# SHDN-CURRENT-S12-V00-Buzzer.net
KiCad netlist of a schematic drawn in Altium Designer
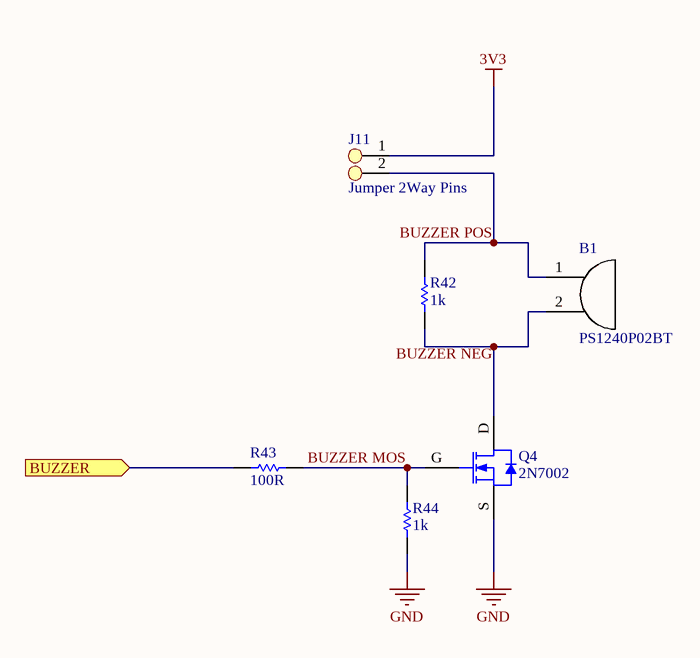
[diagram p0: SHDN-CURRENT-S12-V00-Buzzer.SchDoc]

(export (version "E")
  (design (tool "Eeschema 10.0.6"))
  (components
    (comp (ref "B1")
      (value "PS1240P02BT")
      (footprint "PS1240P02BT")
      (description "Buzzers Transducer, Externally Driven Piezo 3V 4kHz 60dB @ 3V, 10cm Through Hole PC Pins")
      (libsource (lib "QUTMS_BuzzerLibrary") (part "PS1240P02BT"))
    )
    (comp (ref "J11")
      (value "Jumper 2Way Pins")
      (footprint "Jumper_2Way_Pin")
      (description "Jumper 2Way Side Pins")
      (libsource (lib "QUTMS_JumperLibrary") (part "Jumper 2Way Side Pins"))
    )
    (comp (ref "Q4")
      (value "2N7002")
      (footprint "SOT23-3")
      (libsource (lib "QUTMS_MOSFETLibrary") (part "2N7002"))
    )
    (comp (ref "R42")
      (value "1k")
      (footprint "Res_ThinFilm_0603")
      (description "Resistor, SMD, 1k, 0.1W, 5%, 0603")
      (libsource (lib "StandardResistors") (part "1k 5% 0603"))
    )
    (comp (ref "R43")
      (value "100R")
      (footprint "Res_ThinFilm_0603")
      (description "Resistor, SMD, 100R, 0.1W, 5%, 0603")
      (libsource (lib "StandardResistors") (part "100R 5%, 0603"))
    )
    (comp (ref "R44")
      (value "1k")
      (footprint "Res_ThinFilm_0603")
      (description "Resistor, SMD, 1k, 0.1W, 5%, 0603")
      (libsource (lib "StandardResistors") (part "1k 5% 0603"))
    )
  )
  (nets
    (net (code "1") (name "/BUZZER") (class "Default")
      (node (ref "R43") (pin "1") (pinfunction "1_1") (pintype "passive"))
    )
    (net (code "2") (name "/BUZZER MOS") (class "Default")
      (node (ref "Q4") (pin "G") (pinfunction "G_G") (pintype "passive"))
      (node (ref "R43") (pin "2") (pinfunction "2_2") (pintype "passive"))
      (node (ref "R44") (pin "1") (pinfunction "1_1") (pintype "passive"))
    )
    (net (code "3") (name "/BUZZER NEG") (class "Default")
      (node (ref "B1") (pin "2") (pinfunction "2_2") (pintype "passive"))
      (node (ref "Q4") (pin "D") (pinfunction "D_D") (pintype "passive"))
      (node (ref "R42") (pin "1") (pinfunction "1_1") (pintype "passive"))
    )
    (net (code "4") (name "/BUZZER POS") (class "Default")
      (node (ref "B1") (pin "1") (pinfunction "1_1") (pintype "passive"))
      (node (ref "J11") (pin "2") (pinfunction "2_2") (pintype "passive"))
      (node (ref "R42") (pin "2") (pinfunction "2_2") (pintype "passive"))
    )
    (net (code "5") (name "3V3") (class "Default")
      (node (ref "J11") (pin "1") (pinfunction "1_1") (pintype "passive"))
    )
    (net (code "6") (name "GND") (class "Default")
      (node (ref "Q4") (pin "S") (pinfunction "S_S") (pintype "passive"))
      (node (ref "R44") (pin "2") (pinfunction "2_2") (pintype "passive"))
    )
  )
)
